# power.net
KiCad netlist of a schematic drawn in Altium Designer
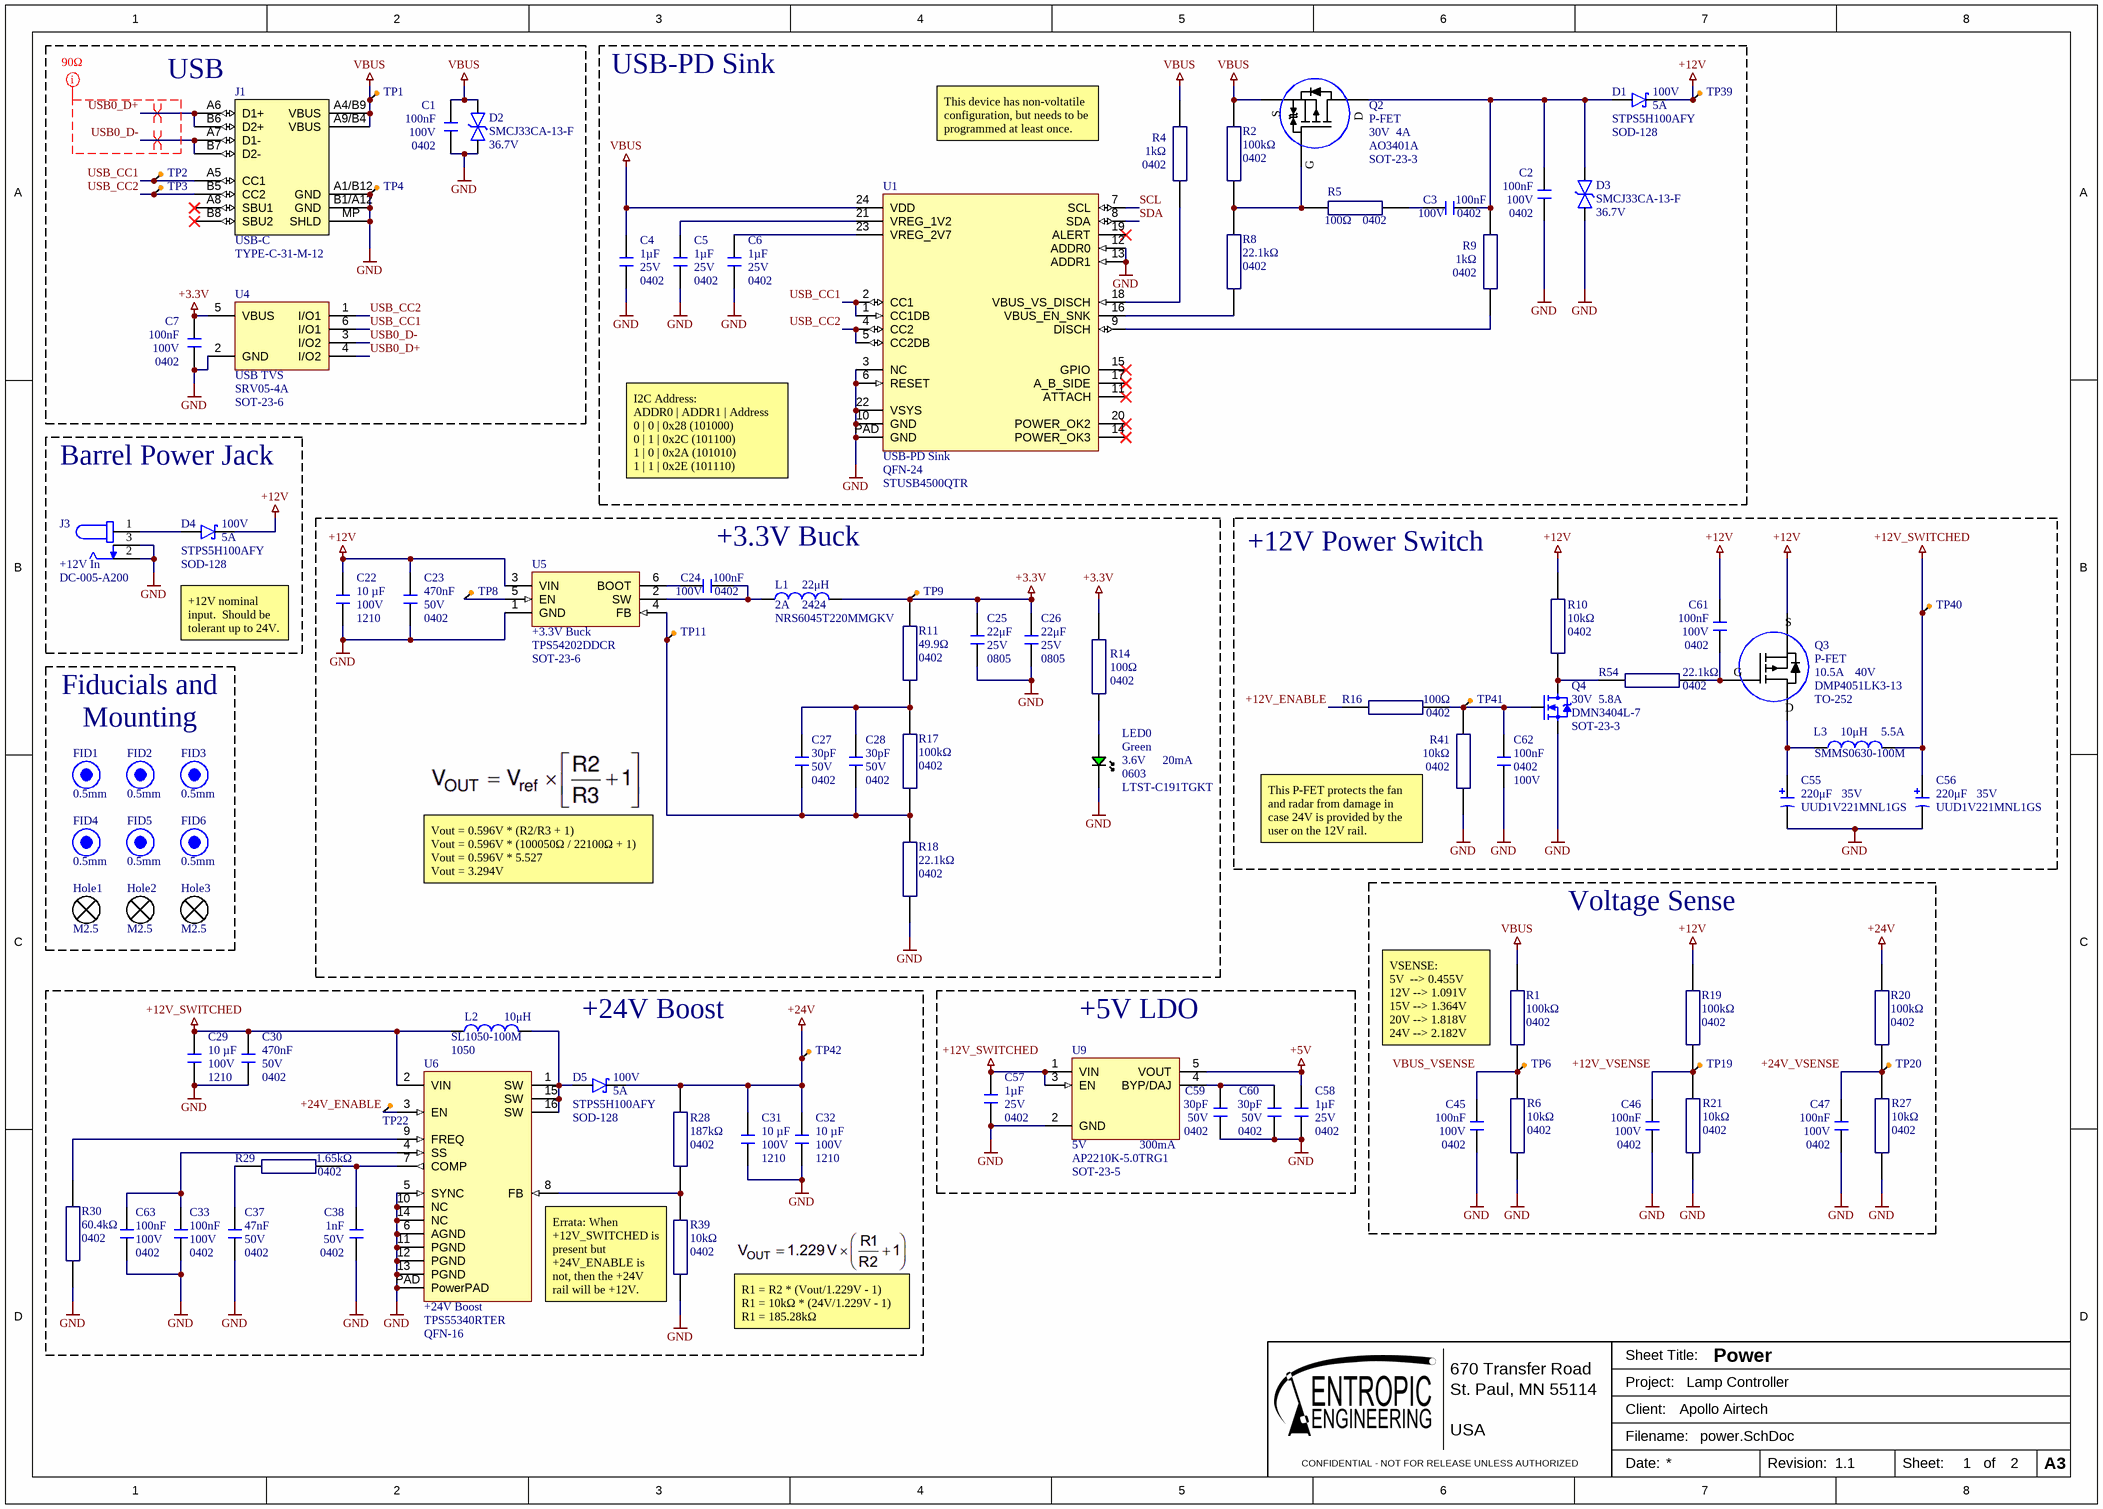
[diagram p0: power.SchDoc]

(export (version "E")
  (design (tool "Eeschema 10.0.6"))
  (components
    (comp (ref "C1")
      (value "100nF")
      (footprint "0402_capacitor")
      (description "100 nF, 100 V, X7R, 0402 Chip capacitor")
      (fields
        (field (name "MANUFACTURER") "Murata")
        (field (name "CASE/PACKAGE") "0402")
        (field (name "MANUFACTURER PART NUMBER") "GRM155R62A104KE14D")
        (field (name "RATED DC VOLTAGE (URDC)") "100V")
      )
      (libsource (lib "lamp_controller") (part "GRM155R62A104KE14D"))
    )
    (comp (ref "C2")
      (value "100nF")
      (footprint "0402_capacitor")
      (description "100 nF, 100 V, X7R, 0402 Chip capacitor")
      (fields
        (field (name "MANUFACTURER") "Murata")
        (field (name "CASE/PACKAGE") "0402")
        (field (name "MANUFACTURER PART NUMBER") "GRM155R62A104KE14D")
        (field (name "RATED DC VOLTAGE (URDC)") "100V")
      )
      (libsource (lib "lamp_controller") (part "GRM155R62A104KE14D"))
    )
    (comp (ref "C3")
      (value "100nF")
      (footprint "0402_capacitor")
      (description "100 nF, 100 V, X7R, 0402 Chip capacitor")
      (fields
        (field (name "MANUFACTURER") "Murata")
        (field (name "CASE/PACKAGE") "0402")
        (field (name "MANUFACTURER PART NUMBER") "GRM155R62A104KE14D")
        (field (name "RATED DC VOLTAGE (URDC)") "100V")
      )
      (libsource (lib "lamp_controller") (part "GRM155R62A104KE14D"))
    )
    (comp (ref "C4")
      (value "GRM155R61E105KA12D")
      (footprint "0402_capacitor")
      (description "1 µF, 25 V, X5R, 0402 Chip capacitor")
      (fields
        (field (name "MANUFACTURER") "Murata")
        (field (name "HOUSE_PART_NUMBER") "C-1uF-0402-002")
        (field (name "SIZE CODE") "0402")
        (field (name "CAPACITANCE") "1µF")
        (field (name "VOLTAGE") "25V")
      )
      (libsource (lib "lamp_controller") (part "GRM155R61E105KA12D"))
    )
    (comp (ref "C5")
      (value "GRM155R61E105KA12D")
      (footprint "0402_capacitor")
      (description "1 µF, 25 V, X5R, 0402 Chip capacitor")
      (fields
        (field (name "MANUFACTURER") "Murata")
        (field (name "HOUSE_PART_NUMBER") "C-1uF-0402-002")
        (field (name "SIZE CODE") "0402")
        (field (name "CAPACITANCE") "1µF")
        (field (name "VOLTAGE") "25V")
      )
      (libsource (lib "lamp_controller") (part "GRM155R61E105KA12D"))
    )
    (comp (ref "C6")
      (value "GRM155R61E105KA12D")
      (footprint "0402_capacitor")
      (description "1 µF, 25 V, X5R, 0402 Chip capacitor")
      (fields
        (field (name "MANUFACTURER") "Murata")
        (field (name "HOUSE_PART_NUMBER") "C-1uF-0402-002")
        (field (name "SIZE CODE") "0402")
        (field (name "CAPACITANCE") "1µF")
        (field (name "VOLTAGE") "25V")
      )
      (libsource (lib "lamp_controller") (part "GRM155R61E105KA12D"))
    )
    (comp (ref "C7")
      (value "100nF")
      (footprint "0402_capacitor")
      (description "100 nF, 100 V, X7R, 0402 Chip capacitor")
      (fields
        (field (name "MANUFACTURER") "Murata")
        (field (name "CASE/PACKAGE") "0402")
        (field (name "MANUFACTURER PART NUMBER") "GRM155R62A104KE14D")
        (field (name "RATED DC VOLTAGE (URDC)") "100V")
      )
      (libsource (lib "lamp_controller") (part "GRM155R62A104KE14D"))
    )
    (comp (ref "C22")
      (value "GRM32EC72A106KE05L")
      (footprint "1210_capacitor")
      (description "10 µF, 100 V, 1210 Ceramic capacitor")
      (fields
        (field (name "MANUFACTURER") "Murata")
        (field (name "TOLERANCE") "10%")
        (field (name "VOLTAGE RATING") "100V")
        (field (name "CASE/PACKAGE") "1210")
        (field (name "CAPACITANCE") "10 µF")
      )
      (libsource (lib "lamp_controller") (part "GRM32EC72A106KE05L"))
    )
    (comp (ref "C23")
      (value "GRM155R61H474KE11D")
      (footprint "0402_capacitor")
      (description "470 nF, 50 V, X5R, 0402 Chip capacitor")
      (fields
        (field (name "MANUFACTURER") "Murata")
        (field (name "TOLERANCE") "10%")
        (field (name "PACKAGE") "0402")
        (field (name "VOLTAGE RATING (DC)") "50V")
        (field (name "CAPACITANCE") "470nF")
      )
      (libsource (lib "lamp_controller") (part "GRM155R61H474KE11D"))
    )
    (comp (ref "C24")
      (value "100nF")
      (footprint "0402_capacitor")
      (description "100 nF, 100 V, X7R, 0402 Chip capacitor")
      (fields
        (field (name "MANUFACTURER") "Murata")
        (field (name "CASE/PACKAGE") "0402")
        (field (name "MANUFACTURER PART NUMBER") "GRM155R62A104KE14D")
        (field (name "RATED DC VOLTAGE (URDC)") "100V")
      )
      (libsource (lib "lamp_controller") (part "GRM155R62A104KE14D"))
    )
    (comp (ref "C25")
      (value "22μF")
      (footprint "0805_capacitor")
      (description "22 μF, 25 V, X5R, 0805 Chip capacitor")
      (fields
        (field (name "MANUFACTURER") "Murata")
        (field (name "MANUFACTURER PART NUMBER") "GRT21BR61E226ME13L")
        (field (name "RATED DC VOLTAGE (URDC)") "25V")
        (field (name "CASE/PACKAGE") "0805")
      )
      (libsource (lib "lamp_controller") (part "GRT21BR61E226ME13L"))
    )
    (comp (ref "C26")
      (value "22μF")
      (footprint "0805_capacitor")
      (description "22 μF, 25 V, X5R, 0805 Chip capacitor")
      (fields
        (field (name "MANUFACTURER") "Murata")
        (field (name "MANUFACTURER PART NUMBER") "GRT21BR61E226ME13L")
        (field (name "RATED DC VOLTAGE (URDC)") "25V")
        (field (name "CASE/PACKAGE") "0805")
      )
      (libsource (lib "lamp_controller") (part "GRT21BR61E226ME13L"))
    )
    (comp (ref "C27")
      (value "30pF")
      (footprint "0402_capacitor")
      (description "30 pF, 50 V, C0G, 0402 Chip capacitor")
      (fields
        (field (name "MANUFACTURER") "Murata")
        (field (name "MANUFACTURER PART NUMBER") "GCM1555C1H300FA16D")
        (field (name "RATED DC VOLTAGE (URDC)") "50V")
        (field (name "CASE/PACKAGE") "0402")
      )
      (libsource (lib "lamp_controller") (part "GCM1555C1H300FA16D"))
    )
    (comp (ref "C28")
      (value "30pF")
      (footprint "0402_capacitor")
      (description "30 pF, 50 V, C0G, 0402 Chip capacitor")
      (fields
        (field (name "MANUFACTURER") "Murata")
        (field (name "MANUFACTURER PART NUMBER") "GCM1555C1H300FA16D")
        (field (name "RATED DC VOLTAGE (URDC)") "50V")
        (field (name "CASE/PACKAGE") "0402")
      )
      (libsource (lib "lamp_controller") (part "GCM1555C1H300FA16D"))
    )
    (comp (ref "C29")
      (value "GRM32EC72A106KE05L")
      (footprint "1210_capacitor")
      (description "10 µF, 100 V, 1210 Ceramic capacitor")
      (fields
        (field (name "MANUFACTURER") "Murata")
        (field (name "TOLERANCE") "10%")
        (field (name "VOLTAGE RATING") "100V")
        (field (name "CASE/PACKAGE") "1210")
        (field (name "CAPACITANCE") "10 µF")
      )
      (libsource (lib "lamp_controller") (part "GRM32EC72A106KE05L"))
    )
    (comp (ref "C30")
      (value "GRM155R61H474KE11D")
      (footprint "0402_capacitor")
      (description "470 nF, 50 V, X5R, 0402 Chip capacitor")
      (fields
        (field (name "MANUFACTURER") "Murata")
        (field (name "TOLERANCE") "10%")
        (field (name "PACKAGE") "0402")
        (field (name "VOLTAGE RATING (DC)") "50V")
        (field (name "CAPACITANCE") "470nF")
      )
      (libsource (lib "lamp_controller") (part "GRM155R61H474KE11D"))
    )
    (comp (ref "C31")
      (value "GRM32EC72A106KE05L")
      (footprint "1210_capacitor")
      (description "10 µF, 100 V, 1210 Ceramic capacitor")
      (fields
        (field (name "MANUFACTURER") "Murata")
        (field (name "TOLERANCE") "10%")
        (field (name "VOLTAGE RATING") "100V")
        (field (name "CASE/PACKAGE") "1210")
        (field (name "CAPACITANCE") "10 µF")
      )
      (libsource (lib "lamp_controller") (part "GRM32EC72A106KE05L"))
    )
    (comp (ref "C32")
      (value "GRM32EC72A106KE05L")
      (footprint "1210_capacitor")
      (description "10 µF, 100 V, 1210 Ceramic capacitor")
      (fields
        (field (name "MANUFACTURER") "Murata")
        (field (name "TOLERANCE") "10%")
        (field (name "VOLTAGE RATING") "100V")
        (field (name "CASE/PACKAGE") "1210")
        (field (name "CAPACITANCE") "10 µF")
      )
      (libsource (lib "lamp_controller") (part "GRM32EC72A106KE05L"))
    )
    (comp (ref "C33")
      (value "100nF")
      (footprint "0402_capacitor")
      (description "100 nF, 100 V, X7R, 0402 Chip capacitor")
      (fields
        (field (name "MANUFACTURER") "Murata")
        (field (name "MANUFACTURER PART NUMBER") "GRM155R62A104KE14D")
        (field (name "CASE/PACKAGE") "0402")
        (field (name "RATED DC VOLTAGE (URDC)") "100V")
      )
      (libsource (lib "lamp_controller") (part "GRM155R62A104KE14D"))
    )
    (comp (ref "C37")
      (value "GRM155R71H473KE14D")
      (footprint "0402_capacitor")
      (description "47 nF, 50 V, X7R, 0402 Chip capacitor")
      (fields
        (field (name "MANUFACTURER") "Murata")
        (field (name "HOUSE_PART_NUMBER") "C-47nF-0402-001")
        (field (name "CASE CODE (IMPERIAL)") "0402")
        (field (name "CAPACITANCE") "47nF")
        (field (name "VOLTAGE RATING") "50V")
      )
      (libsource (lib "lamp_controller") (part "GRM155R71H473KE14D"))
    )
    (comp (ref "C38")
      (value "CC0402KRX7R9BB102")
      (footprint "0402_capacitor")
      (description "1 nF, 50 V, X7R, 0402 Chip capacitor")
      (fields
        (field (name "MANUFACTURER") "Yageo")
        (field (name "TOLERANCE") "10%")
        (field (name "CASE/PACKAGE") "0402")
        (field (name "CAPACITANCE") "1nF")
        (field (name "VOLTAGE RATING") "50V")
      )
      (libsource (lib "lamp_controller") (part "CC0402KRX7R9BB102"))
    )
    (comp (ref "C45")
      (value "100nF")
      (footprint "0402_capacitor")
      (description "100 nF, 100 V, X7R, 0402 Chip capacitor")
      (fields
        (field (name "MANUFACTURER") "Murata")
        (field (name "CASE/PACKAGE") "0402")
        (field (name "MANUFACTURER PART NUMBER") "GRM155R62A104KE14D")
        (field (name "RATED DC VOLTAGE (URDC)") "100V")
      )
      (libsource (lib "lamp_controller") (part "GRM155R62A104KE14D"))
    )
    (comp (ref "C46")
      (value "100nF")
      (footprint "0402_capacitor")
      (description "100 nF, 100 V, X7R, 0402 Chip capacitor")
      (fields
        (field (name "MANUFACTURER") "Murata")
        (field (name "CASE/PACKAGE") "0402")
        (field (name "MANUFACTURER PART NUMBER") "GRM155R62A104KE14D")
        (field (name "RATED DC VOLTAGE (URDC)") "100V")
      )
      (libsource (lib "lamp_controller") (part "GRM155R62A104KE14D"))
    )
    (comp (ref "C47")
      (value "100nF")
      (footprint "0402_capacitor")
      (description "100 nF, 100 V, X7R, 0402 Chip capacitor")
      (fields
        (field (name "MANUFACTURER") "Murata")
        (field (name "CASE/PACKAGE") "0402")
        (field (name "MANUFACTURER PART NUMBER") "GRM155R62A104KE14D")
        (field (name "RATED DC VOLTAGE (URDC)") "100V")
      )
      (libsource (lib "lamp_controller") (part "GRM155R62A104KE14D"))
    )
    (comp (ref "C55")
      (value "UUD1V221MNL1GS")
      (footprint "UUD1V221MNL1GS")
      (description "220 μF, 35 V, 8mm Electrolytic capacitor")
      (fields
        (field (name "MANUFACTURER") "Nichicon")
        (field (name "MANUFACTURER PART NUMBER") "UUD1V221MNL1GS")
        (field (name "RATED DC VOLTAGE (URDC)") "35V")
        (field (name "CAPACITANCE") "220μF")
      )
      (libsource (lib "lamp_controller") (part "UUD1V221MNL1GS"))
    )
    (comp (ref "C56")
      (value "UUD1V221MNL1GS")
      (footprint "UUD1V221MNL1GS")
      (description "220 μF, 35 V, 8mm Electrolytic capacitor")
      (fields
        (field (name "MANUFACTURER") "Nichicon")
        (field (name "MANUFACTURER PART NUMBER") "UUD1V221MNL1GS")
        (field (name "RATED DC VOLTAGE (URDC)") "35V")
        (field (name "CAPACITANCE") "220μF")
      )
      (libsource (lib "lamp_controller") (part "UUD1V221MNL1GS"))
    )
    (comp (ref "C57")
      (value "GRM155R61E105KA12D")
      (footprint "0402_capacitor")
      (description "1 µF, 25 V, X5R, 0402 Chip capacitor")
      (fields
        (field (name "MANUFACTURER") "Murata")
        (field (name "HOUSE_PART_NUMBER") "C-1uF-0402-002")
        (field (name "SIZE CODE") "0402")
        (field (name "CAPACITANCE") "1µF")
        (field (name "VOLTAGE") "25V")
      )
      (libsource (lib "lamp_controller") (part "GRM155R61E105KA12D"))
    )
    (comp (ref "C58")
      (value "GRM155R61E105KA12D")
      (footprint "0402_capacitor")
      (description "1 µF, 25 V, X5R, 0402 Chip capacitor")
      (fields
        (field (name "MANUFACTURER") "Murata")
        (field (name "HOUSE_PART_NUMBER") "C-1uF-0402-002")
        (field (name "SIZE CODE") "0402")
        (field (name "CAPACITANCE") "1µF")
        (field (name "VOLTAGE") "25V")
      )
      (libsource (lib "lamp_controller") (part "GRM155R61E105KA12D"))
    )
    (comp (ref "C59")
      (value "30pF")
      (footprint "0402_capacitor")
      (description "30 pF, 50 V, C0G, 0402 Chip capacitor")
      (fields
        (field (name "MANUFACTURER") "Murata")
        (field (name "MANUFACTURER PART NUMBER") "GCM1555C1H300FA16D")
        (field (name "RATED DC VOLTAGE (URDC)") "50V")
        (field (name "CASE/PACKAGE") "0402")
      )
      (libsource (lib "lamp_controller") (part "GCM1555C1H300FA16D"))
    )
    (comp (ref "C60")
      (value "30pF")
      (footprint "0402_capacitor")
      (description "30 pF, 50 V, C0G, 0402 Chip capacitor")
      (fields
        (field (name "MANUFACTURER") "Murata")
        (field (name "MANUFACTURER PART NUMBER") "GCM1555C1H300FA16D")
        (field (name "RATED DC VOLTAGE (URDC)") "50V")
        (field (name "CASE/PACKAGE") "0402")
      )
      (libsource (lib "lamp_controller") (part "GCM1555C1H300FA16D"))
    )
    (comp (ref "C61")
      (value "100nF")
      (footprint "0402_capacitor")
      (description "100 nF, 100 V, X7R, 0402 Chip capacitor")
      (fields
        (field (name "MANUFACTURER") "Murata")
        (field (name "CASE/PACKAGE") "0402")
        (field (name "MANUFACTURER PART NUMBER") "GRM155R62A104KE14D")
        (field (name "RATED DC VOLTAGE (URDC)") "100V")
      )
      (libsource (lib "lamp_controller") (part "GRM155R62A104KE14D"))
    )
    (comp (ref "C62")
      (value "100nF")
      (footprint "0402_capacitor")
      (description "100 nF, 100 V, X7R, 0402 Chip capacitor")
      (fields
        (field (name "MANUFACTURER") "Murata")
        (field (name "CASE/PACKAGE") "0402")
        (field (name "MANUFACTURER PART NUMBER") "GRM155R62A104KE14D")
        (field (name "RATED DC VOLTAGE (URDC)") "100V")
      )
      (libsource (lib "lamp_controller") (part "GRM155R62A104KE14D"))
    )
    (comp (ref "C63")
      (value "100nF")
      (footprint "0402_capacitor")
      (description "100 nF, 100 V, X7R, 0402 Chip capacitor")
      (fields
        (field (name "MANUFACTURER") "Murata")
        (field (name "MANUFACTURER PART NUMBER") "GRM155R62A104KE14D")
        (field (name "CASE/PACKAGE") "0402")
        (field (name "RATED DC VOLTAGE (URDC)") "100V")
      )
      (libsource (lib "lamp_controller") (part "GRM155R62A104KE14D"))
    )
    (comp (ref "D1")
      (value "STPS5H100AFY")
      (footprint "SOD128")
      (description "Schottky diode, 100V, 5A, SOD-128")
      (fields
        (field (name "MANUFACTURER") "STMicroelectronics")
        (field (name "MANUFACTURER PART NUMBER") "STPS5H100AFY")
        (field (name "PACKAGE") "SOD-128")
        (field (name "CURRENT") "5A")
        (field (name "REP PK REVERSE VOLTAGE-MAX") "100V")
      )
      (libsource (lib "lamp_controller") (part "STPS5H100AFY"))
    )
    (comp (ref "D2")
      (value "SMCJ33CA-13-F")
      (footprint "SMCJ33CA-13-F")
      (description "TVS diode, Trans Voltage Suppressor Diode, 1500W, 33V V(RWM), Bidirectional, 1 Element, Silicon")
      (fields
        (field (name "MANUFACTURER") "Diodes")
        (field (name "MANUFACTURER PART NUMBER") "SMCJ33CA-13-F")
        (field (name "MIN BREAKDOWN VOLTAGE") "36.7V")
      )
      (libsource (lib "lamp_controller") (part "SMCJ33CA-13-F"))
    )
    (comp (ref "D3")
      (value "SMCJ33CA-13-F")
      (footprint "SMCJ33CA-13-F")
      (description "TVS diode, Trans Voltage Suppressor Diode, 1500W, 33V V(RWM), Bidirectional, 1 Element, Silicon")
      (fields
        (field (name "MANUFACTURER") "Diodes")
        (field (name "MANUFACTURER PART NUMBER") "SMCJ33CA-13-F")
        (field (name "MIN BREAKDOWN VOLTAGE") "36.7V")
      )
      (libsource (lib "lamp_controller") (part "SMCJ33CA-13-F"))
    )
    (comp (ref "D4")
      (value "STPS5H100AFY")
      (footprint "SOD128")
      (description "Schottky diode, 100V, 5A, SOD-128")
      (fields
        (field (name "MANUFACTURER") "STMicroelectronics")
        (field (name "MANUFACTURER PART NUMBER") "STPS5H100AFY")
        (field (name "PACKAGE") "SOD-128")
        (field (name "CURRENT") "5A")
        (field (name "REP PK REVERSE VOLTAGE-MAX") "100V")
      )
      (libsource (lib "lamp_controller") (part "STPS5H100AFY"))
    )
    (comp (ref "D5")
      (value "STPS5H100AFY")
      (footprint "SOD128")
      (description "Schottky diode, 100V, 5A, SOD-128")
      (fields
        (field (name "MANUFACTURER") "STMicroelectronics")
        (field (name "MANUFACTURER PART NUMBER") "STPS5H100AFY")
        (field (name "PACKAGE") "SOD-128")
        (field (name "CURRENT") "5A")
        (field (name "REP PK REVERSE VOLTAGE-MAX") "100V")
      )
      (libsource (lib "lamp_controller") (part "STPS5H100AFY"))
    )
    (comp (ref "FID1")
      (value "FID?")
      (footprint "fiducial-0.5")
      (description "0.5mm round fiducial")
      (fields (field (name "PACKAGE") "0.5mm"))
      (libsource (lib "lamp_controller") (part "fiducial-0.5"))
    )
    (comp (ref "FID2")
      (value "FID?")
      (footprint "fiducial-0.5")
      (description "0.5mm round fiducial")
      (fields (field (name "PACKAGE") "0.5mm"))
      (libsource (lib "lamp_controller") (part "fiducial-0.5"))
    )
    (comp (ref "FID3")
      (value "FID?")
      (footprint "fiducial-0.5")
      (description "0.5mm round fiducial")
      (fields (field (name "PACKAGE") "0.5mm"))
      (libsource (lib "lamp_controller") (part "fiducial-0.5"))
    )
    (comp (ref "FID4")
      (value "FID?")
      (footprint "fiducial-0.5")
      (description "0.5mm round fiducial")
      (fields (field (name "PACKAGE") "0.5mm"))
      (libsource (lib "lamp_controller") (part "fiducial-0.5"))
    )
    (comp (ref "FID5")
      (value "FID?")
      (footprint "fiducial-0.5")
      (description "0.5mm round fiducial")
      (fields (field (name "PACKAGE") "0.5mm"))
      (libsource (lib "lamp_controller") (part "fiducial-0.5"))
    )
    (comp (ref "FID6")
      (value "FID?")
      (footprint "fiducial-0.5")
      (description "0.5mm round fiducial")
      (fields (field (name "PACKAGE") "0.5mm"))
      (libsource (lib "lamp_controller") (part "fiducial-0.5"))
    )
    (comp (ref "Hole1")
      (value "M2.5")
      (footprint "m2.5_hole_no_pad")
      (description "M2.5 clearance hole")
      (libsource (lib "lamp_controller") (part "m2.5_hole_no_pad"))
    )
    (comp (ref "Hole2")
      (value "M2.5")
      (footprint "m2.5_hole_no_pad")
      (description "M2.5 clearance hole")
      (libsource (lib "lamp_controller") (part "m2.5_hole_no_pad"))
    )
    (comp (ref "Hole3")
      (value "M2.5")
      (footprint "m2.5_hole_no_pad")
      (description "M2.5 clearance hole")
      (libsource (lib "lamp_controller") (part "m2.5_hole_no_pad"))
    )
    (comp (ref "J1")
      (value "USB-C")
      (footprint "USB_C_2.0_M12")
      (description "USB-C 2.0 Female Connector")
      (fields
        (field (name "MANUFACTURER") "Global Connector Technology")
        (field (name "ALTERNATE PART NUMBER") "USB4105-GF-A")
        (field (name "MANUFACTURER PART NUMBER") "TYPE-C-31-M-12")
      )
      (libsource (lib "lamp_controller") (part "USB4105-GF-A"))
    )
    (comp (ref "J3")
      (value "+12V In")
      (footprint "DC-005-A200")
      (description "5.5 mm x 2 mm, 30V, 3A Barrel jack")
      (fields (field (name "MANUFACTURER") "Xunpu") (field (name "MANUFACTURER PART NUMBER") "DC-005-A200"))
      (libsource (lib "lamp_controller") (part "DC-005-A200"))
    )
    (comp (ref "L1")
      (value "NRS6045T220MMGKV")
      (footprint "2424_inductor")
      (description "22 μH, 2 A, 20%, 2424 Inductor")
      (fields
        (field (name "MANUFACTURER") "Taiyo Yuden")
        (field (name "TOLERANCE") "20%")
        (field (name "MANUFACTURER PART NUMBER") "NRS6045T220MMGKV")
        (field (name "CASE/SIZE CODE") "2424")
        (field (name "MAX CURRENT RATING") "2A")
        (field (name "INDUCTANCE-NOM (L)") "22μH")
      )
      (libsource (lib "lamp_controller") (part "NRS6045T220MMGKV"))
    )
    (comp (ref "L2")
      (value "SL1050-100M")
      (footprint "1050_inductor")
      (description "10 μH, 8A, 1050 Inductor")
      (fields
        (field (name "MANUFACTURER") "TECHFUSE")
        (field (name "INDUCTANCE") "10μH")
        (field (name "PACKAGE") "1050")
        (field (name "MANUFACTURER PART NUMBER") "SL1050-100M")
      )
      (libsource (lib "lamp_controller") (part "SL1050-100M"))
    )
    (comp (ref "L3")
      (value "SMMS0630-100M")
      (footprint "SMMS0630")
      (description "10 μH, 5.5 A, 6.6mm x 7.3mm inductor")
      (fields
        (field (name "MANUFACTURER") "SXN")
        (field (name "SATURATION CURRENT") "5.5A")
        (field (name "INDUCTANCE") "10μH")
        (field (name "MANUFACTURER PART NUMBER") "SMMS0630-100M")
      )
      (libsource (lib "lamp_controller") (part "SMMS0630-100M"))
    )
    (comp (ref "LED0")
      (value "LTST-C191TGKT")
      (footprint "0603_diode")
      (description "Green LED, 0603")
      (fields
        (field (name "MANUFACTURER") "Vishay Lite-On")
        (field (name "FORWARD CURRENT-MAX") "20mA")
        (field (name "FORWARD VOLTAGE-MAX") "3.6V")
        (field (name "COLOR") "Green")
        (field (name "PACKAGE") "0603")
        (field (name "MANUFACTURER PART NUMBER") "LTST-C191TGKT")
      )
      (libsource (lib "lamp_controller") (part "LTST-C191TGKT"))
    )
    (comp (ref "Q2")
      (value "P-FET")
      (footprint "SOT95P280X115-3N")
      (description "P-FET, 30V, 4A, SOT-23-3")
      (fields
        (field (name "MANUFACTURER") "Alpha & Omega Semiconductor")
        (field (name "MANUFACTURER PART NUMBER") "AO3401A")
        (field (name "PACKAGE") "SOT-23-3")
        (field (name "DS BREAKDOWN VOLTAGE-MIN") "30V")
        (field (name "DRAIN CURRENT-MAX (ID)") "4A")
      )
      (libsource (lib "lamp_controller") (part "AO3401A"))
    )
    (comp (ref "Q3")
      (value "P-FET")
      (footprint "TO-252")
      (description "P-FET, 40V, 10.5A, TO-252")
      (fields
        (field (name "MANUFACTURER") "Diodes Zetex")
        (field (name "MANUFACTURER PART NUMBER") "DMP4051LK3-13")
        (field (name "CONTINUOUS DRAIN CURRENT (ID)") "10.5A")
        (field (name "DRAIN TO SOURCE VOLTAGE (VDSS)") "40V")
        (field (name "POLARITY") "P-FET")
        (field (name "CASE/PACKAGE") "TO-252")
      )
      (libsource (lib "lamp_controller") (part "DMP4051LK3-13"))
    )
    (comp (ref "Q4")
      (value "DMN3404L-7")
      (footprint "SOT-23-3")
      (description "N-FET, 30 V, 5.8 A, SOT-23-3")
      (fields
        (field (name "MANUFACTURER") "Diodes")
        (field (name "PACKAGE") "SOT-23-3")
        (field (name "DS BREAKDOWN VOLTAGE-MIN") "30V")
        (field (name "DRAIN CURRENT-MAX (ID)") "5.8A")
        (field (name "MANUFACTURER PART NUMBER") "DMN3404L-7")
      )
      (libsource (lib "lamp_controller") (part "DMN3404L-7"))
    )
    (comp (ref "R1")
      (value "100kΩ")
      (footprint "0402_resistor")
      (description "100 kΩ, 0402 Chip resistor")
      (fields
        (field (name "MANUFACTURER") "Stackpole Electronics")
        (field (name "MANUFACTURER PART NUMBER") "RMCF0402FT100K")
        (field (name "CASE/PACKAGE") "0402")
      )
      (libsource (lib "lamp_controller") (part "RMCF0402FT100K"))
    )
    (comp (ref "R2")
      (value "100kΩ")
      (footprint "0402_resistor")
      (description "100 kΩ, 0402 Chip resistor")
      (fields
        (field (name "MANUFACTURER") "Stackpole Electronics")
        (field (name "MANUFACTURER PART NUMBER") "RMCF0402FT100K")
        (field (name "CASE/PACKAGE") "0402")
      )
      (libsource (lib "lamp_controller") (part "RMCF0402FT100K"))
    )
    (comp (ref "R4")
      (value "CR0402-FX-1001GLF")
      (footprint "0402_resistor")
      (description "1 kΩ, 0402 Chip resistor")
      (fields
        (field (name "MANUFACTURER") "Bourns")
        (field (name "TOLERANCE") "1%")
        (field (name "SIZE CODE") "0402")
        (field (name "RESISTANCE") "1kΩ")
      )
      (libsource (lib "lamp_controller") (part "CR0402-FX-1001GLF"))
    )
    (comp (ref "R5")
      (value "RMCF0402FT100R")
      (footprint "0402_resistor")
      (description "100 Ω, 0402 Chip resistor")
      (fields
        (field (name "MANUFACTURER") "Stackpole Electronics")
        (field (name "TOLERANCE") "1%")
        (field (name "CASE CODE (IMPERIAL)") "0402")
        (field (name "RESISTANCE") "100Ω")
      )
      (libsource (lib "lamp_controller") (part "RMCF0402FT100R"))
    )
    (comp (ref "R6")
      (value "RMCF0402FT10K0")
      (footprint "0402_resistor")
      (description "10 kΩ, 0402 Chip resistor")
      (fields
        (field (name "MANUFACTURER") "Stackpole Electronics")
        (field (name "TOLERANCE") "1%")
        (field (name "CASE CODE (IMPERIAL)") "0402")
        (field (name "RESISTANCE") "10kΩ")
      )
      (libsource (lib "lamp_controller") (part "RMCF0402FT10K0"))
    )
    (comp (ref "R8")
      (value "22.1kΩ")
      (footprint "0402_resistor")
      (description "22.1 kΩ, 1%, 0402 Resistor")
      (fields
        (field (name "MANUFACTURER") "Yageo")
        (field (name "MANUFACTURER PART NUMBER") "RC0402FR-0722K1L")
        (field (name "CASE/PACKAGE") "0402")
      )
      (libsource (lib "lamp_controller") (part "RC0402FR-0722K1L"))
    )
    (comp (ref "R9")
      (value "CR0402-FX-1001GLF")
      (footprint "0402_resistor")
      (description "1 kΩ, 0402 Chip resistor")
      (fields
        (field (name "MANUFACTURER") "Bourns")
        (field (name "TOLERANCE") "1%")
        (field (name "SIZE CODE") "0402")
        (field (name "RESISTANCE") "1kΩ")
      )
      (libsource (lib "lamp_controller") (part "CR0402-FX-1001GLF"))
    )
    (comp (ref "R10")
      (value "RMCF0402FT10K0")
      (footprint "0402_resistor")
      (description "10 kΩ, 0402 Chip resistor")
      (fields
        (field (name "MANUFACTURER") "Stackpole Electronics")
        (field (name "TOLERANCE") "1%")
        (field (name "CASE CODE (IMPERIAL)") "0402")
        (field (name "RESISTANCE") "10kΩ")
      )
      (libsource (lib "lamp_controller") (part "RMCF0402FT10K0"))
    )
    (comp (ref "R11")
      (value "RMCF0402FT49R9")
      (footprint "0402_resistor")
      (description "49.9 Ω, 0402 Chip resistor")
      (fields
        (field (name "MANUFACTURER") "Stackpole Electronics")
        (field (name "TOLERANCE") "1%")
        (field (name "RESISTANCE") "49.9Ω")
        (field (name "CASE CODE (IMPERIAL)") "0402")
      )
      (libsource (lib "lamp_controller") (part "RMCF0402FT49R9"))
    )
    (comp (ref "R14")
      (value "RMCF0402FT100R")
      (footprint "0402_resistor")
      (description "100 Ω, 0402 Chip resistor")
      (fields
        (field (name "MANUFACTURER") "Stackpole Electronics")
        (field (name "TOLERANCE") "1%")
        (field (name "CASE CODE (IMPERIAL)") "0402")
        (field (name "RESISTANCE") "100Ω")
      )
      (libsource (lib "lamp_controller") (part "RMCF0402FT100R"))
    )
    (comp (ref "R16")
      (value "RMCF0402FT100R")
      (footprint "0402_resistor")
      (description "100 Ω, 0402 Chip resistor")
      (fields
        (field (name "MANUFACTURER") "Stackpole Electronics")
        (field (name "TOLERANCE") "1%")
        (field (name "CASE CODE (IMPERIAL)") "0402")
        (field (name "RESISTANCE") "100Ω")
      )
      (libsource (lib "lamp_controller") (part "RMCF0402FT100R"))
    )
    (comp (ref "R17")
      (value "100kΩ")
      (footprint "0402_resistor")
      (description "100 kΩ, 0402 Chip resistor")
      (fields
        (field (name "MANUFACTURER") "Stackpole Electronics")
        (field (name "MANUFACTURER PART NUMBER") "RMCF0402FT100K")
        (field (name "CASE/PACKAGE") "0402")
      )
      (libsource (lib "lamp_controller") (part "RMCF0402FT100K"))
    )
    (comp (ref "R18")
      (value "22.1kΩ")
      (footprint "0402_resistor")
      (description "22.1 kΩ, 1%, 0402 Resistor")
      (fields
        (field (name "MANUFACTURER") "Yageo")
        (field (name "MANUFACTURER PART NUMBER") "RC0402FR-0722K1L")
        (field (name "CASE/PACKAGE") "0402")
      )
      (libsource (lib "lamp_controller") (part "RC0402FR-0722K1L"))
    )
    (comp (ref "R19")
      (value "100kΩ")
      (footprint "0402_resistor")
      (description "100 kΩ, 0402 Chip resistor")
      (fields
        (field (name "MANUFACTURER") "Stackpole Electronics")
        (field (name "MANUFACTURER PART NUMBER") "RMCF0402FT100K")
        (field (name "CASE/PACKAGE") "0402")
      )
      (libsource (lib "lamp_controller") (part "RMCF0402FT100K"))
    )
    (comp (ref "R20")
      (value "100kΩ")
      (footprint "0402_resistor")
      (description "100 kΩ, 0402 Chip resistor")
      (fields
        (field (name "MANUFACTURER") "Stackpole Electronics")
        (field (name "MANUFACTURER PART NUMBER") "RMCF0402FT100K")
        (field (name "CASE/PACKAGE") "0402")
      )
      (libsource (lib "lamp_controller") (part "RMCF0402FT100K"))
    )
    (comp (ref "R21")
      (value "RMCF0402FT10K0")
      (footprint "0402_resistor")
      (description "10 kΩ, 0402 Chip resistor")
      (fields
        (field (name "MANUFACTURER") "Stackpole Electronics")
        (field (name "TOLERANCE") "1%")
        (field (name "CASE CODE (IMPERIAL)") "0402")
        (field (name "RESISTANCE") "10kΩ")
      )
      (libsource (lib "lamp_controller") (part "RMCF0402FT10K0"))
    )
    (comp (ref "R27")
      (value "RMCF0402FT10K0")
      (footprint "0402_resistor")
      (description "10 kΩ, 0402 Chip resistor")
      (fields
        (field (name "MANUFACTURER") "Stackpole Electronics")
        (field (name "TOLERANCE") "1%")
        (field (name "CASE CODE (IMPERIAL)") "0402")
        (field (name "RESISTANCE") "10kΩ")
      )
      (libsource (lib "lamp_controller") (part "RMCF0402FT10K0"))
    )
    (comp (ref "R28")
      (value "AC0402FR-07187KL")
      (footprint "0402_resistor")
      (description "187 kΩ, 1%, 0402 Chip resistor")
      (fields
        (field (name "MANUFACTURER") "Yageo")
        (field (name "TOLERANCE") "1%")
        (field (name "CASE/PACKAGE") "0402")
        (field (name "RESISTANCE") "187kΩ")
      )
      (libsource (lib "lamp_controller") (part "AC0402FR-07187KL"))
    )
    (comp (ref "R29")
      (value "RC0402FR-071K65L")
      (footprint "0402_resistor")
      (description "1.65 kΩ, 1%, 0402 Chip capacitor")
      (fields
        (field (name "MANUFACTURER") "Yageo")
        (field (name "TOLERANCE") "1%")
        (field (name "RESISTANCE") "1.65kΩ")
        (field (name "CASE/PACKAGE") "0402")
      )
      (libsource (lib "lamp_controller") (part "RC0402FR-071K65L"))
    )
    (comp (ref "R30")
      (value "RC0402FR-0760K4L")
      (footprint "0402_resistor")
      (description "60.4 kΩ, 1%, 0402 Chip resistor")
      (fields
        (field (name "MANUFACTURER") "Yageo")
        (field (name "TOLERANCE") "1%")
        (field (name "RESISTANCE") "60.4kΩ")
        (field (name "CASE/PACKAGE") "0402")
      )
      (libsource (lib "lamp_controller") (part "RC0402FR-0760K4L"))
    )
    (comp (ref "R39")
      (value "RMCF0402FT10K0")
      (footprint "0402_resistor")
      (description "10 kΩ, 0402 Chip resistor")
      (fields
        (field (name "MANUFACTURER") "Stackpole Electronics")
        (field (name "TOLERANCE") "1%")
        (field (name "CASE CODE (IMPERIAL)") "0402")
        (field (name "RESISTANCE") "10kΩ")
      )
      (libsource (lib "lamp_controller") (part "RMCF0402FT10K0"))
    )
    (comp (ref "R41")
      (value "RMCF0402FT10K0")
      (footprint "0402_resistor")
      (description "10 kΩ, 0402 Chip resistor")
      (fields
        (field (name "MANUFACTURER") "Stackpole Electronics")
        (field (name "TOLERANCE") "1%")
        (field (name "CASE CODE (IMPERIAL)") "0402")
        (field (name "RESISTANCE") "10kΩ")
      )
      (libsource (lib "lamp_controller") (part "RMCF0402FT10K0"))
    )
    (comp (ref "R54")
      (value "22.1kΩ")
      (footprint "0402_resistor")
      (description "22.1 kΩ, 1%, 0402 Resistor")
      (fields
        (field (name "MANUFACTURER") "Yageo")
        (field (name "CASE/PACKAGE") "0402")
        (field (name "TOLERANCE") "1%")
      )
      (libsource (lib "lamp_controller") (part "RC0402FR-0722K1L"))
    )
    (comp (ref "TP1")
      (value "VBUS")
      (footprint "test_point-1")
      (description "Test point")
      (libsource (lib "lamp_controller") (part "test_point-1"))
    )
    (comp (ref "TP2")
      (value "CC1")
      (footprint "test_point-1")
      (description "Test point")
      (libsource (lib "lamp_controller") (part "test_point-1"))
    )
    (comp (ref "TP3")
      (value "CC2")
      (footprint "test_point-1")
      (description "Test point")
      (libsource (lib "lamp_controller") (part "test_point-1"))
    )
    (comp (ref "TP4")
      (value "GND")
      (footprint "test_point-1")
      (description "Test point")
      (libsource (lib "lamp_controller") (part "test_point-1"))
    )
    (comp (ref "TP6")
      (value "VBUS Sense")
      (footprint "test_point-1")
      (description "Test point")
      (libsource (lib "lamp_controller") (part "test_point-1"))
    )
    (comp (ref "TP8")
      (value "Buck EN")
      (footprint "test_point-1")
      (description "Test point")
      (libsource (lib "lamp_controller") (part "test_point-1"))
    )
    (comp (ref "TP9")
      (value "+3.3V")
      (footprint "test_point-1")
      (description "Test point")
      (libsource (lib "lamp_controller") (part "test_point-1"))
    )
    (comp (ref "TP11")
      (value "Buck Feedback")
      (footprint "test_point-1")
      (description "Test point")
      (libsource (lib "lamp_controller") (part "test_point-1"))
    )
    (comp (ref "TP19")
      (value "+12V Sense")
      (footprint "test_point-1")
      (description "Test point")
      (libsource (lib "lamp_controller") (part "test_point-1"))
    )
    (comp (ref "TP20")
      (value "+24V Sense")
      (footprint "test_point-1")
      (description "Test point")
      (libsource (lib "lamp_controller") (part "test_point-1"))
    )
    (comp (ref "TP22")
      (value "+24V Enable")
      (footprint "test_point-1")
      (description "Test point")
      (libsource (lib "lamp_controller") (part "test_point-1"))
    )
    (comp (ref "TP39")
      (value "+12V")
      (footprint "test_point-1")
      (description "Test point")
      (libsource (lib "lamp_controller") (part "test_point-1"))
    )
    (comp (ref "TP40")
      (value "+12V Switched")
      (footprint "test_point-1")
      (description "Test point")
      (libsource (lib "lamp_controller") (part "test_point-1"))
    )
    (comp (ref "TP41")
      (value "+12V Enable")
      (footprint "test_point-1")
      (description "Test point")
      (libsource (lib "lamp_controller") (part "test_point-1"))
    )
    (comp (ref "TP42")
      (value "+24V")
      (footprint "test_point-1")
      (description "Test point")
      (libsource (lib "lamp_controller") (part "test_point-1"))
    )
    (comp (ref "U1")
      (value "USB-PD Sink")
      (footprint "QFN-24")
      (description "USB PD Sink")
      (fields
        (field (name "MANUFACTURER") "STMicroelectronics")
        (field (name "PACKAGE") "QFN-24")
        (field (name "MANUFACTURER PART NUMBER") "STUSB4500QTR")
      )
      (libsource (lib "lamp_controller") (part "STUSB4500QTR"))
    )
    (comp (ref "U4")
      (value "USB TVS")
      (footprint "SOT95P280X110-6N")
      (description "TVS DIODE ARRAY SOT23-6")
      (fields
        (field (name "MANUFACTURER") "SMC Diodes")
        (field (name "CASE/PACKAGE") "SOT-23-6")
        (field (name "MANUFACTURER PART NUMBER") "SRV05-4A")
        (field (name "HOUSE_PART_NUMBER") "SRV05-4A")
      )
      (libsource (lib "lamp_controller") (part "SRV05-4A"))
    )
    (comp (ref "U5")
      (value "+3.3V Buck")
      (footprint "SOT-23-6")
      (description "Switching Regulator, Current-mode, 2A, 500kHz Switching Freq-Max, PDSO6")
      (fields
        (field (name "MANUFACTURER") "Texas Instruments")
        (field (name "CASE/PACKAGE") "SOT-23-6")
        (field (name "MANUFACTURER PART NUMBER") "TPS54202DDCR")
      )
      (libsource (lib "lamp_controller") (part "TPS54202DDCR"))
    )
    (comp (ref "U6")
      (value "+24V Boost")
      (footprint "QDF-16")
      (description "Boost, 32V, 7.75A, QFN-16")
      (fields
        (field (name "MANUFACTURER") "Texas Instruments")
        (field (name "PACKAGE") "QFN-16")
        (field (name "MANUFACTURER PART NUMBER") "TPS55340RTER")
      )
      (libsource (lib "lamp_controller") (part "TPS55340RTER"))
    )
    (comp (ref "U9")
      (value "AP2210K-5.0TRG1")
      (footprint "SOT-23-5")
      (description "5 V, 300 mA LDO, SOT-23-5")
      (fields
        (field (name "MANUFACTURER") "Diodes")
        (field (name "CASE/PACKAGE") "SOT-23-5")
        (field (name "OUTPUT CURRENT1-MAX") "300mA")
        (field (name "OUTPUT VOLTAGE1-NOM") "5V")
        (field (name "MANUFACTURER PART NUMBER") "AP2210K-5.0TRG1")
      )
      (libsource (lib "lamp_controller") (part "AP2210K-5.0TRG1"))
    )
  )
  (nets
    (net (code "1") (name "+3.3V") (class "Default")
      (node (ref "C25") (pin "2") (pinfunction "2_2") (pintype "passive"))
      (node (ref "C26") (pin "2") (pinfunction "2_2") (pintype "passive"))
      (node (ref "C7") (pin "2") (pinfunction "2_2") (pintype "passive"))
      (node (ref "L1") (pin "2") (pinfunction "2_2") (pintype "passive"))
      (node (ref "R11") (pin "2") (pinfunction "2_2") (pintype "passive"))
      (node (ref "R14") (pin "2") (pinfunction "2_2") (pintype "passive"))
      (node (ref "TP9") (pin "1") (pinfunction "1_1") (pintype "passive"))
      (node (ref "U4") (pin "5") (pinfunction "VBUS_5") (pintype "passive"))
    )
    (net (code "2") (name "+5V") (class "Default")
      (node (ref "C58") (pin "2") (pinfunction "2_2") (pintype "passive"))
      (node (ref "U9") (pin "5") (pinfunction "VOUT_5") (pintype "power_in"))
    )
    (net (code "3") (name "+12V") (class "Default")
      (node (ref "C22") (pin "2") (pinfunction "2_2") (pintype "passive"))
      (node (ref "C23") (pin "2") (pinfunction "2_2") (pintype "passive"))
      (node (ref "C61") (pin "2") (pinfunction "2_2") (pintype "passive"))
      (node (ref "D1") (pin "1") (pinfunction "1_1") (pintype "passive"))
      (node (ref "D4") (pin "1") (pinfunction "1_1") (pintype "passive"))
      (node (ref "Q3") (pin "3") (pinfunction "S_3") (pintype "passive"))
      (node (ref "R10") (pin "2") (pinfunction "2_2") (pintype "passive"))
      (node (ref "R19") (pin "2") (pinfunction "2_2") (pintype "passive"))
      (node (ref "TP39") (pin "1") (pinfunction "1_1") (pintype "passive"))
      (node (ref "U5") (pin "3") (pinfunction "VIN_3") (pintype "power_in"))
    )
    (net (code "4") (name "+12V_SWITCHED") (class "Default")
      (node (ref "C29") (pin "2") (pinfunction "2_2") (pintype "passive"))
      (node (ref "C30") (pin "2") (pinfunction "2_2") (pintype "passive"))
      (node (ref "C56") (pin "1") (pinfunction "1_1") (pintype "passive"))
      (node (ref "C57") (pin "2") (pinfunction "2_2") (pintype "passive"))
      (node (ref "L2") (pin "1") (pinfunction "1_1") (pintype "passive"))
      (node (ref "L3") (pin "2") (pinfunction "2_2") (pintype "passive"))
      (node (ref "TP40") (pin "1") (pinfunction "1_1") (pintype "passive"))
      (node (ref "U6") (pin "2") (pinfunction "VIN_2") (pintype "power_in"))
      (node (ref "U9") (pin "1") (pinfunction "VIN_1") (pintype "power_in"))
      (node (ref "U9") (pin "3") (pinfunction "EN_3") (pintype "input"))
    )
    (net (code "5") (name "+24V") (class "Default")
      (node (ref "C31") (pin "2") (pinfunction "2_2") (pintype "passive"))
      (node (ref "C32") (pin "2") (pinfunction "2_2") (pintype "passive"))
      (node (ref "D5") (pin "1") (pinfunction "1_1") (pintype "passive"))
      (node (ref "R20") (pin "2") (pinfunction "2_2") (pintype "passive"))
      (node (ref "R28") (pin "2") (pinfunction "2_2") (pintype "passive"))
      (node (ref "TP42") (pin "1") (pinfunction "1_1") (pintype "passive"))
    )
    (net (code "6") (name "/+12V_ENABLE") (class "Default")
      (node (ref "R16") (pin "1") (pinfunction "1_1") (pintype "passive"))
    )
    (net (code "7") (name "/+12V_VSENSE") (class "Default")
      (node (ref "C46") (pin "2") (pinfunction "2_2") (pintype "passive"))
      (node (ref "R19") (pin "1") (pinfunction "1_1") (pintype "passive"))
      (node (ref "R21") (pin "2") (pinfunction "2_2") (pintype "passive"))
      (node (ref "TP19") (pin "1") (pinfunction "1_1") (pintype "passive"))
    )
    (net (code "8") (name "/+24V_ENABLE") (class "Default")
      (node (ref "TP22") (pin "1") (pinfunction "1_1") (pintype "passive"))
      (node (ref "U6") (pin "3") (pinfunction "EN_3") (pintype "input"))
    )
    (net (code "9") (name "/+24V_VSENSE") (class "Default")
      (node (ref "C47") (pin "2") (pinfunction "2_2") (pintype "passive"))
      (node (ref "R20") (pin "1") (pinfunction "1_1") (pintype "passive"))
      (node (ref "R27") (pin "2") (pinfunction "2_2") (pintype "passive"))
      (node (ref "TP20") (pin "1") (pinfunction "1_1") (pintype "passive"))
    )
    (net (code "10") (name "/SCL") (class "Default")
      (node (ref "U1") (pin "7") (pinfunction "SCL_7") (pintype "bidirectional"))
    )
    (net (code "11") (name "/SDA") (class "Default")
      (node (ref "U1") (pin "8") (pinfunction "SDA_8") (pintype "bidirectional"))
    )
    (net (code "12") (name "/USB0_D+") (class "Default")
      (node (ref "J1") (pin "A6") (pinfunction "D1+_A6") (pintype "bidirectional"))
      (node (ref "J1") (pin "B6") (pinfunction "D2+_B6") (pintype "bidirectional"))
      (node (ref "U4") (pin "4") (pinfunction "I/O2_4") (pintype "passive"))
    )
    (net (code "13") (name "/USB0_D-") (class "Default")
      (node (ref "J1") (pin "A7") (pinfunction "D1-_A7") (pintype "bidirectional"))
      (node (ref "J1") (pin "B7") (pinfunction "D2-_B7") (pintype "bidirectional"))
      (node (ref "U4") (pin "3") (pinfunction "I/O2_3") (pintype "passive"))
    )
    (net (code "14") (name "/USB_CC1") (class "Default")
      (node (ref "J1") (pin "A5") (pinfunction "CC1_A5") (pintype "bidirectional"))
      (node (ref "TP2") (pin "1") (pinfunction "1_1") (pintype "passive"))
      (node (ref "U1") (pin "1") (pinfunction "CC1DB_1") (pintype "input"))
      (node (ref "U1") (pin "2") (pinfunction "CC1_2") (pintype "bidirectional"))
      (node (ref "U4") (pin "6") (pinfunction "I/O1_6") (pintype "passive"))
    )
    (net (code "15") (name "/USB_CC2") (class "Default")
      (node (ref "J1") (pin "B5") (pinfunction "CC2_B5") (pintype "bidirectional"))
      (node (ref "TP3") (pin "1") (pinfunction "1_1") (pintype "passive"))
      (node (ref "U1") (pin "4") (pinfunction "CC2_4") (pintype "bidirectional"))
      (node (ref "U1") (pin "5") (pinfunction "CC2DB_5") (pintype "bidirectional"))
      (node (ref "U4") (pin "1") (pinfunction "I/O1_1") (pintype "passive"))
    )
    (net (code "16") (name "/VBUS_VSENSE") (class "Default")
      (node (ref "C45") (pin "2") (pinfunction "2_2") (pintype "passive"))
      (node (ref "R1") (pin "1") (pinfunction "1_1") (pintype "passive"))
      (node (ref "R6") (pin "2") (pinfunction "2_2") (pintype "passive"))
      (node (ref "TP6") (pin "1") (pinfunction "1_1") (pintype "passive"))
    )
    (net (code "17") (name "GND") (class "Default")
      (node (ref "C1") (pin "1") (pinfunction "1_1") (pintype "passive"))
      (node (ref "C2") (pin "1") (pinfunction "1_1") (pintype "passive"))
      (node (ref "C22") (pin "1") (pinfunction "1_1") (pintype "passive"))
      (node (ref "C23") (pin "1") (pinfunction "1_1") (pintype "passive"))
      (node (ref "C25") (pin "1") (pinfunction "1_1") (pintype "passive"))
      (node (ref "C26") (pin "1") (pinfunction "1_1") (pintype "passive"))
      (node (ref "C29") (pin "1") (pinfunction "1_1") (pintype "passive"))
      (node (ref "C30") (pin "1") (pinfunction "1_1") (pintype "passive"))
      (node (ref "C31") (pin "1") (pinfunction "1_1") (pintype "passive"))
      (node (ref "C32") (pin "1") (pinfunction "1_1") (pintype "passive"))
      (node (ref "C33") (pin "1") (pinfunction "1_1") (pintype "passive"))
      (node (ref "C37") (pin "1") (pinfunction "1_1") (pintype "passive"))
      (node (ref "C38") (pin "1") (pinfunction "1_1") (pintype "passive"))
      (node (ref "C4") (pin "1") (pinfunction "1_1") (pintype "passive"))
      (node (ref "C45") (pin "1") (pinfunction "1_1") (pintype "passive"))
      (node (ref "C46") (pin "1") (pinfunction "1_1") (pintype "passive"))
      (node (ref "C47") (pin "1") (pinfunction "1_1") (pintype "passive"))
      (node (ref "C5") (pin "1") (pinfunction "1_1") (pintype "passive"))
      (node (ref "C55") (pin "2") (pinfunction "2_2") (pintype "passive"))
      (node (ref "C56") (pin "2") (pinfunction "2_2") (pintype "passive"))
      (node (ref "C57") (pin "1") (pinfunction "1_1") (pintype "passive"))
      (node (ref "C58") (pin "1") (pinfunction "1_1") (pintype "passive"))
      (node (ref "C59") (pin "1") (pinfunction "1_1") (pintype "passive"))
      (node (ref "C6") (pin "1") (pinfunction "1_1") (pintype "passive"))
      (node (ref "C60") (pin "1") (pinfunction "1_1") (pintype "passive"))
      (node (ref "C62") (pin "1") (pinfunction "1_1") (pintype "passive"))
      (node (ref "C63") (pin "1") (pinfunction "1_1") (pintype "passive"))
      (node (ref "C7") (pin "1") (pinfunction "1_1") (pintype "passive"))
      (node (ref "D2") (pin "2") (pinfunction "2_2") (pintype "passive"))
      (node (ref "D3") (pin "2") (pinfunction "2_2") (pintype "passive"))
      (node (ref "J1") (pin "A1/B12") (pinfunction "GND_A1/B12") (pintype "power_in"))
      (node (ref "J1") (pin "B1/A12") (pinfunction "GND_B1/A12") (pintype "power_in"))
      (node (ref "J1") (pin "MP") (pinfunction "SHLD_MP") (pintype "passive"))
      (node (ref "J3") (pin "2") (pinfunction "SLEEVE_2") (pintype "passive"))
      (node (ref "J3") (pin "3") (pinfunction "SWITCH_3") (pintype "passive"))
      (node (ref "LED0") (pin "2") (pinfunction "K_2") (pintype "passive"))
      (node (ref "Q4") (pin "2") (pinfunction "S_2") (pintype "passive"))
      (node (ref "R18") (pin "1") (pinfunction "1_1") (pintype "passive"))
      (node (ref "R21") (pin "1") (pinfunction "1_1") (pintype "passive"))
      (node (ref "R27") (pin "1") (pinfunction "1_1") (pintype "passive"))
      (node (ref "R30") (pin "1") (pinfunction "1_1") (pintype "passive"))
      (node (ref "R39") (pin "1") (pinfunction "1_1") (pintype "passive"))
      (node (ref "R41") (pin "1") (pinfunction "1_1") (pintype "passive"))
      (node (ref "R6") (pin "1") (pinfunction "1_1") (pintype "passive"))
      (node (ref "TP4") (pin "1") (pinfunction "1_1") (pintype "passive"))
      (node (ref "U1") (pin "10") (pinfunction "GND_10") (pintype "power_in"))
      (node (ref "U1") (pin "12") (pinfunction "ADDR0_12") (pintype "input"))
      (node (ref "U1") (pin "13") (pinfunction "ADDR1_13") (pintype "input"))
      (node (ref "U1") (pin "22") (pinfunction "VSYS_22") (pintype "power_in"))
      (node (ref "U1") (pin "3") (pinfunction "NC_3") (pintype "passive"))
      (node (ref "U1") (pin "6") (pinfunction "RESET_6") (pintype "input"))
      (node (ref "U1") (pin "PAD") (pinfunction "GND_PAD") (pintype "power_in"))
      (node (ref "U4") (pin "2") (pinfunction "GND_2") (pintype "passive"))
      (node (ref "U5") (pin "1") (pinfunction "GND_1") (pintype "power_in"))
      (node (ref "U6") (pin "10") (pinfunction "NC_10") (pintype "power_in"))
      (node (ref "U6") (pin "11") (pinfunction "PGND_11") (pintype "power_in"))
      (node (ref "U6") (pin "12") (pinfunction "PGND_12") (pintype "power_in"))
      (node (ref "U6") (pin "13") (pinfunction "PGND_13") (pintype "power_in"))
      (node (ref "U6") (pin "14") (pinfunction "NC_14") (pintype "power_in"))
      (node (ref "U6") (pin "5") (pinfunction "SYNC_5") (pintype "input"))
      (node (ref "U6") (pin "6") (pinfunction "AGND_6") (pintype "power_in"))
      (node (ref "U6") (pin "PAD") (pinfunction "PowerPAD_PAD") (pintype "power_in"))
      (node (ref "U9") (pin "2") (pinfunction "GND_2") (pintype "power_in"))
    )
    (net (code "18") (name "Net-(C3-Pad2)") (class "Default")
      (node (ref "C3") (pin "2") (pinfunction "2_2") (pintype "passive"))
      (node (ref "R5") (pin "2") (pinfunction "2_2") (pintype "passive"))
    )
    (net (code "19") (name "Net-(C27-Pad2)") (class "Default")
      (node (ref "C27") (pin "2") (pinfunction "2_2") (pintype "passive"))
      (node (ref "C28") (pin "2") (pinfunction "2_2") (pintype "passive"))
      (node (ref "R11") (pin "1") (pinfunction "1_1") (pintype "passive"))
      (node (ref "R17") (pin "2") (pinfunction "2_2") (pintype "passive"))
    )
    (net (code "20") (name "Net-(C37-Pad2)") (class "Default")
      (node (ref "C37") (pin "2") (pinfunction "2_2") (pintype "passive"))
      (node (ref "R29") (pin "1") (pinfunction "1_1") (pintype "passive"))
    )
    (net (code "21") (name "Net-(D5-Pad2)") (class "Default")
      (node (ref "D5") (pin "2") (pinfunction "2_2") (pintype "passive"))
      (node (ref "L2") (pin "2") (pinfunction "2_2") (pintype "passive"))
      (node (ref "U6") (pin "1") (pinfunction "SW_1") (pintype "power_in"))
      (node (ref "U6") (pin "15") (pinfunction "SW_15") (pintype "power_in"))
      (node (ref "U6") (pin "16") (pinfunction "SW_16") (pintype "power_in"))
    )
    (net (code "22") (name "Net-(J3-TIP)") (class "Default")
      (node (ref "D4") (pin "2") (pinfunction "2_2") (pintype "passive"))
      (node (ref "J3") (pin "1") (pinfunction "TIP_1") (pintype "passive"))
    )
    (net (code "23") (name "Net-(LED0-A)") (class "Default")
      (node (ref "LED0") (pin "1") (pinfunction "A_1") (pintype "passive"))
      (node (ref "R14") (pin "1") (pinfunction "1_1") (pintype "passive"))
    )
    (net (code "24") (name "Net-(Q2-D)") (class "Default")
      (node (ref "C2") (pin "2") (pinfunction "2_2") (pintype "passive"))
      (node (ref "C3") (pin "1") (pinfunction "1_1") (pintype "passive"))
      (node (ref "D1") (pin "2") (pinfunction "2_2") (pintype "passive"))
      (node (ref "D3") (pin "1") (pinfunction "1_1") (pintype "passive"))
      (node (ref "Q2") (pin "3") (pinfunction "D_3") (pintype "passive"))
      (node (ref "R9") (pin "2") (pinfunction "2_2") (pintype "passive"))
    )
    (net (code "25") (name "Net-(Q2-G)") (class "Default")
      (node (ref "Q2") (pin "1") (pinfunction "G_1") (pintype "passive"))
      (node (ref "R2") (pin "1") (pinfunction "1_1") (pintype "passive"))
      (node (ref "R5") (pin "1") (pinfunction "1_1") (pintype "passive"))
      (node (ref "R8") (pin "2") (pinfunction "2_2") (pintype "passive"))
    )
    (net (code "26") (name "Net-(Q3-D)") (class "Default")
      (node (ref "C55") (pin "1") (pinfunction "1_1") (pintype "passive"))
      (node (ref "L3") (pin "1") (pinfunction "1_1") (pintype "passive"))
      (node (ref "Q3") (pin "2") (pinfunction "D_2") (pintype "passive"))
    )
    (net (code "27") (name "Net-(Q3-G)") (class "Default")
      (node (ref "C61") (pin "1") (pinfunction "1_1") (pintype "passive"))
      (node (ref "Q3") (pin "1") (pinfunction "G_1") (pintype "passive"))
      (node (ref "R54") (pin "2") (pinfunction "2_2") (pintype "passive"))
    )
    (net (code "28") (name "Net-(Q4-D)") (class "Default")
      (node (ref "Q4") (pin "3") (pinfunction "D_3") (pintype "passive"))
      (node (ref "R10") (pin "1") (pinfunction "1_1") (pintype "passive"))
      (node (ref "R54") (pin "1") (pinfunction "1_1") (pintype "passive"))
    )
    (net (code "29") (name "Net-(Q4-G)") (class "Default")
      (node (ref "C62") (pin "2") (pinfunction "2_2") (pintype "passive"))
      (node (ref "Q4") (pin "1") (pinfunction "G_1") (pintype "passive"))
      (node (ref "R16") (pin "2") (pinfunction "2_2") (pintype "passive"))
      (node (ref "R41") (pin "2") (pinfunction "2_2") (pintype "passive"))
      (node (ref "TP41") (pin "1") (pinfunction "1_1") (pintype "passive"))
    )
    (net (code "30") (name "Net-(U1-DISCH)") (class "Default")
      (node (ref "R9") (pin "1") (pinfunction "1_1") (pintype "passive"))
      (node (ref "U1") (pin "9") (pinfunction "DISCH_9") (pintype "bidirectional"))
    )
    (net (code "31") (name "Net-(U1-VBUS_EN_SNK)") (class "Default")
      (node (ref "R8") (pin "1") (pinfunction "1_1") (pintype "passive"))
      (node (ref "U1") (pin "16") (pinfunction "VBUS_EN_SNK_16") (pintype "open_collector"))
    )
    (net (code "32") (name "Net-(U1-VBUS_VS_DISCH)") (class "Default")
      (node (ref "R4") (pin "1") (pinfunction "1_1") (pintype "passive"))
      (node (ref "U1") (pin "18") (pinfunction "VBUS_VS_DISCH_18") (pintype "input"))
    )
    (net (code "33") (name "Net-(U1-VREG_1V2)") (class "Default")
      (node (ref "C5") (pin "2") (pinfunction "2_2") (pintype "passive"))
      (node (ref "U1") (pin "21") (pinfunction "VREG_1V2_21") (pintype "power_in"))
    )
    (net (code "34") (name "Net-(U1-VREG_2V7)") (class "Default")
      (node (ref "C6") (pin "2") (pinfunction "2_2") (pintype "passive"))
      (node (ref "U1") (pin "23") (pinfunction "VREG_2V7_23") (pintype "power_in"))
    )
    (net (code "35") (name "Net-(U5-BOOT)") (class "Default")
      (node (ref "C24") (pin "2") (pinfunction "2_2") (pintype "passive"))
      (node (ref "U5") (pin "6") (pinfunction "BOOT_6") (pintype "power_in"))
    )
    (net (code "36") (name "Net-(U5-EN)") (class "Default")
      (node (ref "TP8") (pin "1") (pinfunction "1_1") (pintype "passive"))
      (node (ref "U5") (pin "5") (pinfunction "EN_5") (pintype "input"))
    )
    (net (code "37") (name "Net-(U5-FB)") (class "Default")
      (node (ref "C27") (pin "1") (pinfunction "1_1") (pintype "passive"))
      (node (ref "C28") (pin "1") (pinfunction "1_1") (pintype "passive"))
      (node (ref "R17") (pin "1") (pinfunction "1_1") (pintype "passive"))
      (node (ref "R18") (pin "2") (pinfunction "2_2") (pintype "passive"))
      (node (ref "TP11") (pin "1") (pinfunction "1_1") (pintype "passive"))
      (node (ref "U5") (pin "4") (pinfunction "FB_4") (pintype "input"))
    )
    (net (code "38") (name "Net-(U5-SW)") (class "Default")
      (node (ref "C24") (pin "1") (pinfunction "1_1") (pintype "passive"))
      (node (ref "L1") (pin "1") (pinfunction "1_1") (pintype "passive"))
      (node (ref "U5") (pin "2") (pinfunction "SW_2") (pintype "power_in"))
    )
    (net (code "39") (name "Net-(U6-COMP)") (class "Default")
      (node (ref "C38") (pin "2") (pinfunction "2_2") (pintype "passive"))
      (node (ref "R29") (pin "2") (pinfunction "2_2") (pintype "passive"))
      (node (ref "U6") (pin "7") (pinfunction "COMP_7") (pintype "output"))
    )
    (net (code "40") (name "Net-(U6-FB)") (class "Default")
      (node (ref "R28") (pin "1") (pinfunction "1_1") (pintype "passive"))
      (node (ref "R39") (pin "2") (pinfunction "2_2") (pintype "passive"))
      (node (ref "U6") (pin "8") (pinfunction "FB_8") (pintype "input"))
    )
    (net (code "41") (name "Net-(U6-FREQ)") (class "Default")
      (node (ref "R30") (pin "2") (pinfunction "2_2") (pintype "passive"))
      (node (ref "U6") (pin "9") (pinfunction "FREQ_9") (pintype "input"))
    )
    (net (code "42") (name "Net-(U6-SS)") (class "Default")
      (node (ref "C33") (pin "2") (pinfunction "2_2") (pintype "passive"))
      (node (ref "C63") (pin "2") (pinfunction "2_2") (pintype "passive"))
      (node (ref "U6") (pin "4") (pinfunction "SS_4") (pintype "input"))
    )
    (net (code "43") (name "Net-(U9-BYP{slash}DAJ)") (class "Default")
      (node (ref "C59") (pin "2") (pinfunction "2_2") (pintype "passive"))
      (node (ref "C60") (pin "2") (pinfunction "2_2") (pintype "passive"))
      (node (ref "U9") (pin "4") (pinfunction "BYP/DAJ_4") (pintype "power_in"))
    )
    (net (code "44") (name "VBUS") (class "Default")
      (node (ref "C1") (pin "2") (pinfunction "2_2") (pintype "passive"))
      (node (ref "C4") (pin "2") (pinfunction "2_2") (pintype "passive"))
      (node (ref "D2") (pin "1") (pinfunction "1_1") (pintype "passive"))
      (node (ref "J1") (pin "A4/B9") (pinfunction "VBUS_A4/B9") (pintype "power_in"))
      (node (ref "J1") (pin "A9/B4") (pinfunction "VBUS_A9/B4") (pintype "power_in"))
      (node (ref "Q2") (pin "2") (pinfunction "S_2") (pintype "passive"))
      (node (ref "R1") (pin "2") (pinfunction "2_2") (pintype "passive"))
      (node (ref "R2") (pin "2") (pinfunction "2_2") (pintype "passive"))
      (node (ref "R4") (pin "2") (pinfunction "2_2") (pintype "passive"))
      (node (ref "TP1") (pin "1") (pinfunction "1_1") (pintype "passive"))
      (node (ref "U1") (pin "24") (pinfunction "VDD_24") (pintype "power_in"))
    )
    (net (code "45") (name "unconnected-(J1-SBU1-PadA8)") (class "Default")
      (node (ref "J1") (pin "A8") (pinfunction "SBU1_A8") (pintype "bidirectional+no_connect"))
    )
    (net (code "46") (name "unconnected-(J1-SBU2-PadB8)") (class "Default")
      (node (ref "J1") (pin "B8") (pinfunction "SBU2_B8") (pintype "bidirectional+no_connect"))
    )
    (net (code "47") (name "unconnected-(U1-ALERT-Pad19)") (class "Default")
      (node (ref "U1") (pin "19") (pinfunction "ALERT_19") (pintype "open_collector+no_connect"))
    )
    (net (code "48") (name "unconnected-(U1-ATTACH-Pad11)") (class "Default")
      (node (ref "U1") (pin "11") (pinfunction "ATTACH_11") (pintype "open_collector+no_connect"))
    )
    (net (code "49") (name "unconnected-(U1-A_B_SIDE-Pad17)") (class "Default")
      (node (ref "U1") (pin "17") (pinfunction "A_B_SIDE_17") (pintype "open_collector+no_connect"))
    )
    (net (code "50") (name "unconnected-(U1-GPIO-Pad15)") (class "Default")
      (node (ref "U1") (pin "15") (pinfunction "GPIO_15") (pintype "open_collector+no_connect"))
    )
    (net (code "51") (name "unconnected-(U1-POWER_OK2-Pad20)") (class "Default")
      (node (ref "U1") (pin "20") (pinfunction "POWER_OK2_20") (pintype "open_collector+no_connect"))
    )
    (net (code "52") (name "unconnected-(U1-POWER_OK3-Pad14)") (class "Default")
      (node (ref "U1") (pin "14") (pinfunction "POWER_OK3_14") (pintype "open_collector+no_connect"))
    )
  )
)
